# powersource_for_Heater.net
KiCad netlist of a schematic drawn in EAGLE
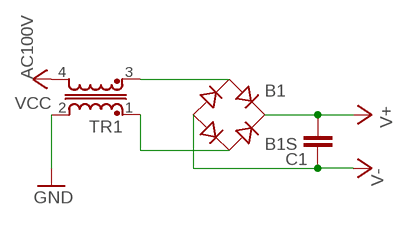
[diagram p0: schematic, sheet 1]

(export (version "E")
  (design (tool "Eeschema 10.0.6"))
  (components
    (comp (ref "B1")
      (value "B1S")
      (footprint "eagle-import:MBS")
      (libsource (lib "eagle-import") (part "BS1"))
    )
    (comp (ref "C1")
      (value "C10/5")
      (footprint "eagle-import:C10B5")
      (libsource (lib "eagle-import") (part "C10/5"))
    )
    (comp (ref "TR1")
      (value "U15-TRANSFORMER")
      (footprint "eagle-import:U15")
      (libsource (lib "eagle-import") (part "U15-TRANSFORMER"))
    )
  )
  (nets
    (net (code "1") (name "GND") (class "Default")
      (node (ref "TR1") (pin "2") (pinfunction "2_2") (pintype "passive"))
    )
    (net (code "2") (name "Net-(B1-PadAC1)") (class "Default")
      (node (ref "B1") (pin "AC1") (pinfunction "AC1_AC1") (pintype "passive"))
      (node (ref "TR1") (pin "3") (pinfunction "3_3") (pintype "passive"))
    )
    (net (code "3") (name "Net-(B1-PadAC2)") (class "Default")
      (node (ref "B1") (pin "AC2") (pinfunction "AC2_AC2") (pintype "passive"))
      (node (ref "TR1") (pin "1") (pinfunction "1_1") (pintype "passive"))
    )
    (net (code "4") (name "V+") (class "Default")
      (node (ref "B1") (pin "+") (pinfunction "+_+") (pintype "passive"))
      (node (ref "B1") (pin "-") (pinfunction "-_-") (pintype "passive"))
      (node (ref "C1") (pin "1") (pinfunction "1_1") (pintype "passive"))
      (node (ref "C1") (pin "2") (pinfunction "2_2") (pintype "passive"))
    )
    (net (code "5") (name "VCC") (class "Default")
      (node (ref "TR1") (pin "4") (pinfunction "4_4") (pintype "passive"))
    )
  )
)
